# POWER_SCH.net
KiCad netlist of a schematic drawn in Altium Designer
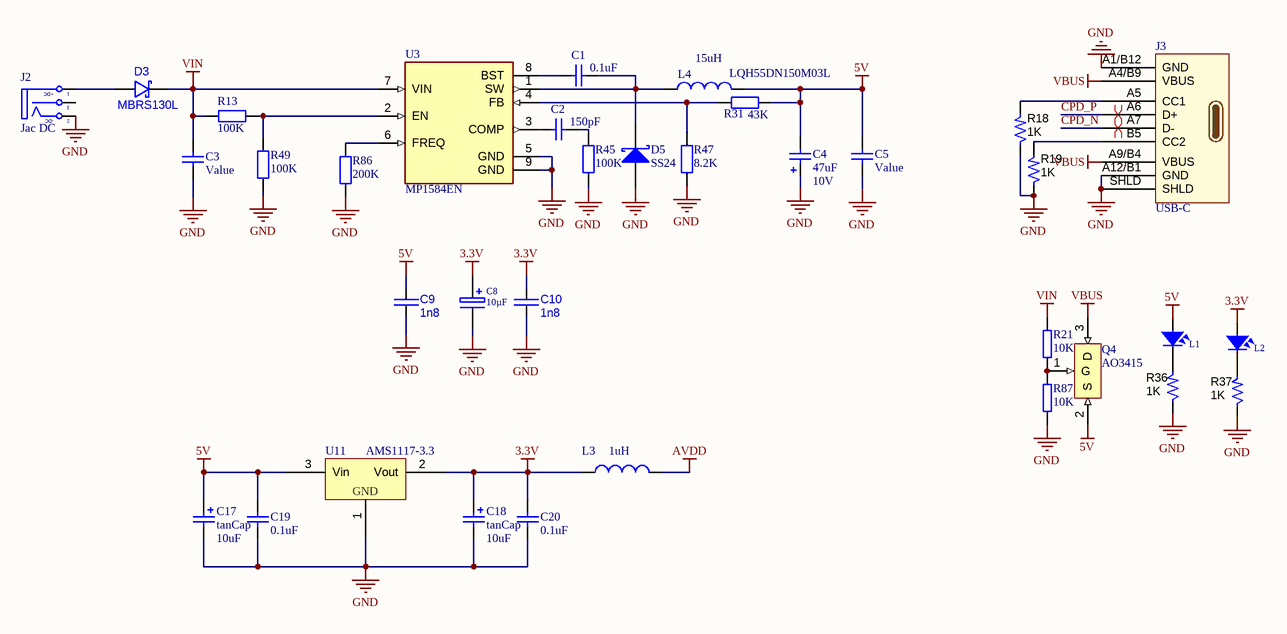
[diagram p0: POWER_SCH.SchDoc]

(export (version "E")
  (design (tool "Eeschema 10.0.6"))
  (components
    (comp (ref "C1")
      (value "0.1uF")
      (footprint "CAP-0603")
      (description "Capacitor")
      (fields (field (name "PUBLISHER") "Altium Limited"))
      (libsource (lib "mp1584") (part "Cap"))
    )
    (comp (ref "C2")
      (value "150pF")
      (footprint "CAP-0603")
      (description "Capacitor")
      (fields (field (name "PUBLISHER") "Altium Limited"))
      (libsource (lib "mp1584") (part "Cap"))
    )
    (comp (ref "C3") (value "Value") (footprint "C1206") (libsource (lib "My Library") (part "Cap SMD 1206")))
    (comp (ref "C4")
      (value "47uF")
      (footprint "Tantal_B")
      (description "Polarized Capacitor (Axial)")
      (fields (field (name "VOLTAGE") "10V") (field (name "PUBLISHER") "Altium Limited"))
      (libsource (lib "mp1584") (part "Cap Pol"))
    )
    (comp (ref "C5") (value "Value") (footprint "C1206") (libsource (lib "My Library") (part "Cap SMD 1206")))
    (comp (ref "C8")
      (value "CAP")
      (footprint "CAPMP3528X210N")
      (fields (field (name "ALTIUM_UNNAMED_1") "10µF"))
      (libsource (lib "WIle_dev_kit") (part "CAP Tatalium"))
    )
    (comp (ref "C9")
      (value "1n8")
      (footprint "CAPC2012X135N")
      (description "Capacitor SMD Cer 1.8nF 10% 50V X7R 0805")
      (fields (field (name "TOLERANCE") "±10%") (field (name "Comment") "approved sub OK"))
      (libsource (lib "WIle_dev_kit") (part "CAP C_0805"))
    )
    (comp (ref "C10")
      (value "1n8")
      (footprint "CAPC2012X135N")
      (description "Capacitor SMD Cer 1.8nF 10% 50V X7R 0805")
      (fields (field (name "TOLERANCE") "±10%") (field (name "Comment") "approved sub OK"))
      (libsource (lib "WIle_dev_kit") (part "CAP C_0805"))
    )
    (comp (ref "C17")
      (value "tanCap")
      (footprint "C1206")
      (description "Polarized Capacitor (Axial)")
      (fields (field (name "ALTIUM_VALUE") "10uF") (field (name "PUBLISHER") "Altium Limited"))
      (libsource (lib "Miscellaneous Devices") (part "Cap Pol2"))
    )
    (comp (ref "C18")
      (value "tanCap")
      (footprint "C1206")
      (description "Polarized Capacitor (Axial)")
      (fields (field (name "ALTIUM_VALUE") "10uF") (field (name "PUBLISHER") "Altium Limited"))
      (libsource (lib "Miscellaneous Devices") (part "Cap Pol2"))
    )
    (comp (ref "C19")
      (value "0.1uF")
      (footprint "C0805")
      (description "Capacitor")
      (fields (field (name "Comment") "Cap") (field (name "PUBLISHER") "Altium Limited"))
      (libsource (lib "Miscellaneous Devices") (part "Cap"))
    )
    (comp (ref "C20")
      (value "0.1uF")
      (footprint "C0805")
      (description "Capacitor")
      (fields (field (name "Comment") "Cap") (field (name "PUBLISHER") "Altium Limited"))
      (libsource (lib "Miscellaneous Devices") (part "Cap"))
    )
    (comp (ref "D3")
      (value "MBRS130L")
      (footprint "DO-214AA")
      (description "Diode Schottky SMD 30V 2A DO-214AA")
      (libsource (lib "My library altium") (part "DIODE_SCHOTTKY_MBRS130L"))
    )
    (comp (ref "D5")
      (value "SS24")
      (footprint "SMB")
      (description "Schottky Diode")
      (fields (field (name "PUBLISHER") "Altium Limited"))
      (libsource (lib "mp1584") (part "D Schottky"))
    )
    (comp (ref "J2")
      (value "Jac DC")
      (footprint "DC-IN")
      (description "Jac DC input")
      (libsource (lib "WIle_dev_kit") (part "DCIN"))
    )
    (comp (ref "J3") (value "USB-C") (footprint "USB-C 8p") (libsource (lib "WIle_dev_kit") (part "USB-C")))
    (comp (ref "L1")
      (value "LED SMD")
      (footprint "SM-LED-0805-Orange")
      (libsource (lib "WIle_dev_kit") (part "LED SMD 0805"))
    )
    (comp (ref "L2")
      (value "LED SMD")
      (footprint "SM-LED-0805-Orange")
      (libsource (lib "WIle_dev_kit") (part "LED SMD 0805"))
    )
    (comp (ref "L3")
      (value "1uH")
      (footprint "C0805")
      (description "Inductor")
      (fields (field (name "PUBLISHER") "Altium Limited"))
      (libsource (lib "Miscellaneous Devices") (part "Inductor"))
    )
    (comp (ref "L4")
      (value "15uH")
      (footprint "Inductor SMD 6.8*6.8*4.5")
      (fields (field (name "MARKA") "LQH55DN150M03L"))
      (libsource (lib "mp1584") (part "Inductor"))
    )
    (comp (ref "Q4") (value "AO3415") (footprint "SOT23-3") (libsource (lib "WIle_dev_kit") (part "AO3415")))
    (comp (ref "R13") (value "100K") (footprint "RES-0603") (libsource (lib "mp1584") (part "Res")))
    (comp (ref "R18")
      (value "1K")
      (footprint "RESC1608N_ZERO")
      (description "Resistor SMD chip 0.0 Ohm 0.1W 0603")
      (fields (field (name "TOLERANCE") "±5%"))
      (libsource (lib "WIle_dev_kit") (part "RES_0603"))
    )
    (comp (ref "R19")
      (value "1K")
      (footprint "RESC1608N_ZERO")
      (description "Resistor SMD chip 0.0 Ohm 0.1W 0603")
      (fields (field (name "TOLERANCE") "±5%"))
      (libsource (lib "WIle_dev_kit") (part "RES_0603"))
    )
    (comp (ref "R21")
      (value "10K")
      (footprint "RESC1608N_ZERO")
      (description "RES SM 0603 10K")
      (fields (field (name "Comment") "Resistor"))
      (libsource (lib "electronpowered") (part "RES-SM-0603-10K"))
    )
    (comp (ref "R31") (value "43K") (footprint "RES-0603") (libsource (lib "mp1584") (part "Res")))
    (comp (ref "R36")
      (value "1K")
      (footprint "RESC1608N_ZERO")
      (description "Resistor SMD chip 0.0 Ohm 0.1W 0603")
      (fields (field (name "TOLERANCE") "±5%"))
      (libsource (lib "WIle_dev_kit") (part "RES_0603"))
    )
    (comp (ref "R37")
      (value "1K")
      (footprint "RESC1608N_ZERO")
      (description "Resistor SMD chip 0.0 Ohm 0.1W 0603")
      (fields (field (name "TOLERANCE") "±5%"))
      (libsource (lib "WIle_dev_kit") (part "RES_0603"))
    )
    (comp (ref "R45") (value "100K") (footprint "RES-0603") (libsource (lib "mp1584") (part "Res")))
    (comp (ref "R47") (value "8.2K") (footprint "RES-0603") (libsource (lib "mp1584") (part "Res")))
    (comp (ref "R49") (value "100K") (footprint "RES-0603") (libsource (lib "mp1584") (part "Res")))
    (comp (ref "R86") (value "200K") (footprint "RES-0603") (libsource (lib "mp1584") (part "Res")))
    (comp (ref "R87")
      (value "10K")
      (footprint "RESC1608N_ZERO")
      (description "RES SM 0603 10K")
      (fields (field (name "Comment") "Resistor"))
      (libsource (lib "electronpowered") (part "RES-SM-0603-10K"))
    )
    (comp (ref "U3")
      (value "MP1584EN")
      (footprint "SOIC127P600X170-9N")
      (fields (field (name "MF") "Monolithic Power"))
      (libsource (lib "MP1584EN") (part "MP1584EN"))
    )
    (comp (ref "U11")
      (value "AMS1117-3.3")
      (footprint "SOT223_M")
      (description "AMS1117-")
      (libsource (lib "qyh") (part "AMS1117"))
    )
  )
  (nets
    (net (code "1") (name "/CPD_N") (class "Default")
      (node (ref "J3") (pin "A7") (pinfunction "D-_A7") (pintype "passive"))
    )
    (net (code "2") (name "/CPD_P") (class "Default")
      (node (ref "J3") (pin "A6") (pinfunction "D+_A6") (pintype "passive"))
    )
    (net (code "3") (name "3.3V") (class "Default")
      (node (ref "C10") (pin "2") (pintype "passive"))
      (node (ref "C18") (pin "1") (pinfunction "1_1") (pintype "passive"))
      (node (ref "C20") (pin "1") (pinfunction "1_1") (pintype "passive"))
      (node (ref "C8") (pin "1") (pintype "passive"))
      (node (ref "L2") (pin "1") (pinfunction "1_1") (pintype "passive"))
      (node (ref "L3") (pin "1") (pinfunction "1_1") (pintype "passive"))
      (node (ref "U11") (pin "2") (pinfunction "Vout_2") (pintype "passive"))
    )
    (net (code "4") (name "5V") (class "Default")
      (node (ref "C17") (pin "1") (pinfunction "1_1") (pintype "passive"))
      (node (ref "C19") (pin "1") (pinfunction "1_1") (pintype "passive"))
      (node (ref "C4") (pin "2") (pinfunction "2_2") (pintype "passive"))
      (node (ref "C5") (pin "2") (pinfunction "2_2") (pintype "passive"))
      (node (ref "C9") (pin "2") (pintype "passive"))
      (node (ref "L1") (pin "1") (pinfunction "1_1") (pintype "passive"))
      (node (ref "L4") (pin "2") (pinfunction "2_2") (pintype "passive"))
      (node (ref "Q4") (pin "2") (pinfunction "S_2") (pintype "input"))
      (node (ref "R31") (pin "2") (pinfunction "2_2") (pintype "passive"))
      (node (ref "U11") (pin "3") (pinfunction "Vin_3") (pintype "passive"))
    )
    (net (code "5") (name "AVDD") (class "Default")
      (node (ref "L3") (pin "2") (pinfunction "2_2") (pintype "passive"))
    )
    (net (code "6") (name "GND") (class "Default")
      (node (ref "C10") (pin "1") (pintype "passive"))
      (node (ref "C17") (pin "2") (pinfunction "2_2") (pintype "passive"))
      (node (ref "C18") (pin "2") (pinfunction "2_2") (pintype "passive"))
      (node (ref "C19") (pin "2") (pinfunction "2_2") (pintype "passive"))
      (node (ref "C20") (pin "2") (pinfunction "2_2") (pintype "passive"))
      (node (ref "C3") (pin "1") (pinfunction "1_1") (pintype "passive"))
      (node (ref "C4") (pin "1") (pinfunction "1_1") (pintype "passive"))
      (node (ref "C5") (pin "1") (pinfunction "1_1") (pintype "passive"))
      (node (ref "C8") (pin "2") (pintype "passive"))
      (node (ref "C9") (pin "1") (pintype "passive"))
      (node (ref "D5") (pin "1") (pinfunction "A_1") (pintype "passive"))
      (node (ref "J2") (pin "2") (pinfunction "TN_2") (pintype "passive"))
      (node (ref "J3") (pin "A1/B12") (pinfunction "GND_A1/B12") (pintype "passive"))
      (node (ref "J3") (pin "A12/B1") (pinfunction "GND_A12/B1") (pintype "passive"))
      (node (ref "J3") (pin "SHLD") (pinfunction "SHLD_SHLD") (pintype "passive"))
      (node (ref "R18") (pin "1") (pinfunction "1_1") (pintype "passive"))
      (node (ref "R19") (pin "1") (pinfunction "1_1") (pintype "passive"))
      (node (ref "R36") (pin "1") (pinfunction "1_1") (pintype "passive"))
      (node (ref "R37") (pin "1") (pinfunction "1_1") (pintype "passive"))
      (node (ref "R45") (pin "2") (pinfunction "2_2") (pintype "passive"))
      (node (ref "R47") (pin "2") (pinfunction "2_2") (pintype "passive"))
      (node (ref "R49") (pin "1") (pinfunction "1_1") (pintype "passive"))
      (node (ref "R86") (pin "1") (pinfunction "1_1") (pintype "passive"))
      (node (ref "R87") (pin "2") (pinfunction "2_2") (pintype "passive"))
      (node (ref "U11") (pin "1") (pinfunction "GND_1") (pintype "passive"))
      (node (ref "U3") (pin "5") (pinfunction "GND_5") (pintype "power_in"))
      (node (ref "U3") (pin "9") (pinfunction "GND_9") (pintype "power_in"))
    )
    (net (code "7") (name "Net-(C2-Pad2)") (class "Default")
      (node (ref "C2") (pin "2") (pinfunction "2_2") (pintype "passive"))
      (node (ref "R45") (pin "1") (pinfunction "1_1") (pintype "passive"))
    )
    (net (code "8") (name "Net-(D5-K)") (class "Default")
      (node (ref "C1") (pin "2") (pinfunction "2_2") (pintype "passive"))
      (node (ref "D5") (pin "2") (pinfunction "K_2") (pintype "passive"))
      (node (ref "L4") (pin "1") (pinfunction "1_1") (pintype "passive"))
      (node (ref "U3") (pin "1") (pinfunction "SW_1") (pintype "output"))
    )
    (net (code "9") (name "Net-(J2-T)") (class "Default")
      (node (ref "D3") (pin "A") (pinfunction "A_A") (pintype "passive"))
      (node (ref "J2") (pin "1") (pinfunction "T_1") (pintype "passive"))
    )
    (net (code "10") (name "Net-(J3-CC1)") (class "Default")
      (node (ref "J3") (pin "A5") (pinfunction "CC1_A5") (pintype "passive"))
      (node (ref "R18") (pin "2") (pinfunction "2_2") (pintype "passive"))
    )
    (net (code "11") (name "Net-(J3-CC2)") (class "Default")
      (node (ref "J3") (pin "B5") (pinfunction "CC2_B5") (pintype "passive"))
      (node (ref "R19") (pin "2") (pinfunction "2_2") (pintype "passive"))
    )
    (net (code "12") (name "Net-(L1-Pad2)") (class "Default")
      (node (ref "L1") (pin "2") (pinfunction "2_2") (pintype "passive"))
      (node (ref "R36") (pin "2") (pinfunction "2_2") (pintype "passive"))
    )
    (net (code "13") (name "Net-(L2-Pad2)") (class "Default")
      (node (ref "L2") (pin "2") (pinfunction "2_2") (pintype "passive"))
      (node (ref "R37") (pin "2") (pinfunction "2_2") (pintype "passive"))
    )
    (net (code "14") (name "Net-(Q4-G)") (class "Default")
      (node (ref "Q4") (pin "1") (pinfunction "G_1") (pintype "input"))
      (node (ref "R21") (pin "2") (pinfunction "2_2") (pintype "passive"))
      (node (ref "R87") (pin "1") (pinfunction "1_1") (pintype "passive"))
    )
    (net (code "15") (name "Net-(U3-BST)") (class "Default")
      (node (ref "C1") (pin "1") (pinfunction "1_1") (pintype "passive"))
      (node (ref "U3") (pin "8") (pinfunction "BST_8") (pintype "passive"))
    )
    (net (code "16") (name "Net-(U3-COMP)") (class "Default")
      (node (ref "C2") (pin "1") (pinfunction "1_1") (pintype "passive"))
      (node (ref "U3") (pin "3") (pinfunction "COMP_3") (pintype "output"))
    )
    (net (code "17") (name "Net-(U3-EN)") (class "Default")
      (node (ref "R13") (pin "2") (pinfunction "2_2") (pintype "passive"))
      (node (ref "R49") (pin "2") (pinfunction "2_2") (pintype "passive"))
      (node (ref "U3") (pin "2") (pinfunction "EN_2") (pintype "input"))
    )
    (net (code "18") (name "Net-(U3-FB)") (class "Default")
      (node (ref "R31") (pin "1") (pinfunction "1_1") (pintype "passive"))
      (node (ref "R47") (pin "1") (pinfunction "1_1") (pintype "passive"))
      (node (ref "U3") (pin "4") (pinfunction "FB_4") (pintype "input"))
    )
    (net (code "19") (name "Net-(U3-FREQ)") (class "Default")
      (node (ref "R86") (pin "2") (pinfunction "2_2") (pintype "passive"))
      (node (ref "U3") (pin "6") (pinfunction "FREQ_6") (pintype "input"))
    )
    (net (code "20") (name "VBUS") (class "Default")
      (node (ref "J3") (pin "A4/B9") (pinfunction "VBUS_A4/B9") (pintype "passive"))
      (node (ref "J3") (pin "A9/B4") (pinfunction "VBUS_A9/B4") (pintype "passive"))
      (node (ref "Q4") (pin "3") (pinfunction "D_3") (pintype "input"))
    )
    (net (code "21") (name "VIN") (class "Default")
      (node (ref "C3") (pin "2") (pinfunction "2_2") (pintype "passive"))
      (node (ref "D3") (pin "K") (pinfunction "K_K") (pintype "passive"))
      (node (ref "R13") (pin "1") (pinfunction "1_1") (pintype "passive"))
      (node (ref "R21") (pin "1") (pinfunction "1_1") (pintype "passive"))
      (node (ref "U3") (pin "7") (pinfunction "VIN_7") (pintype "input"))
    )
    (net (code "22") (name "unconnected-(J2-S-Pad3)") (class "Default")
      (node (ref "J2") (pin "3") (pinfunction "S_3") (pintype "power_in"))
    )
  )
)
